# top_tnb_mns_power.net
KiCad netlist of a schematic drawn in Altium Designer
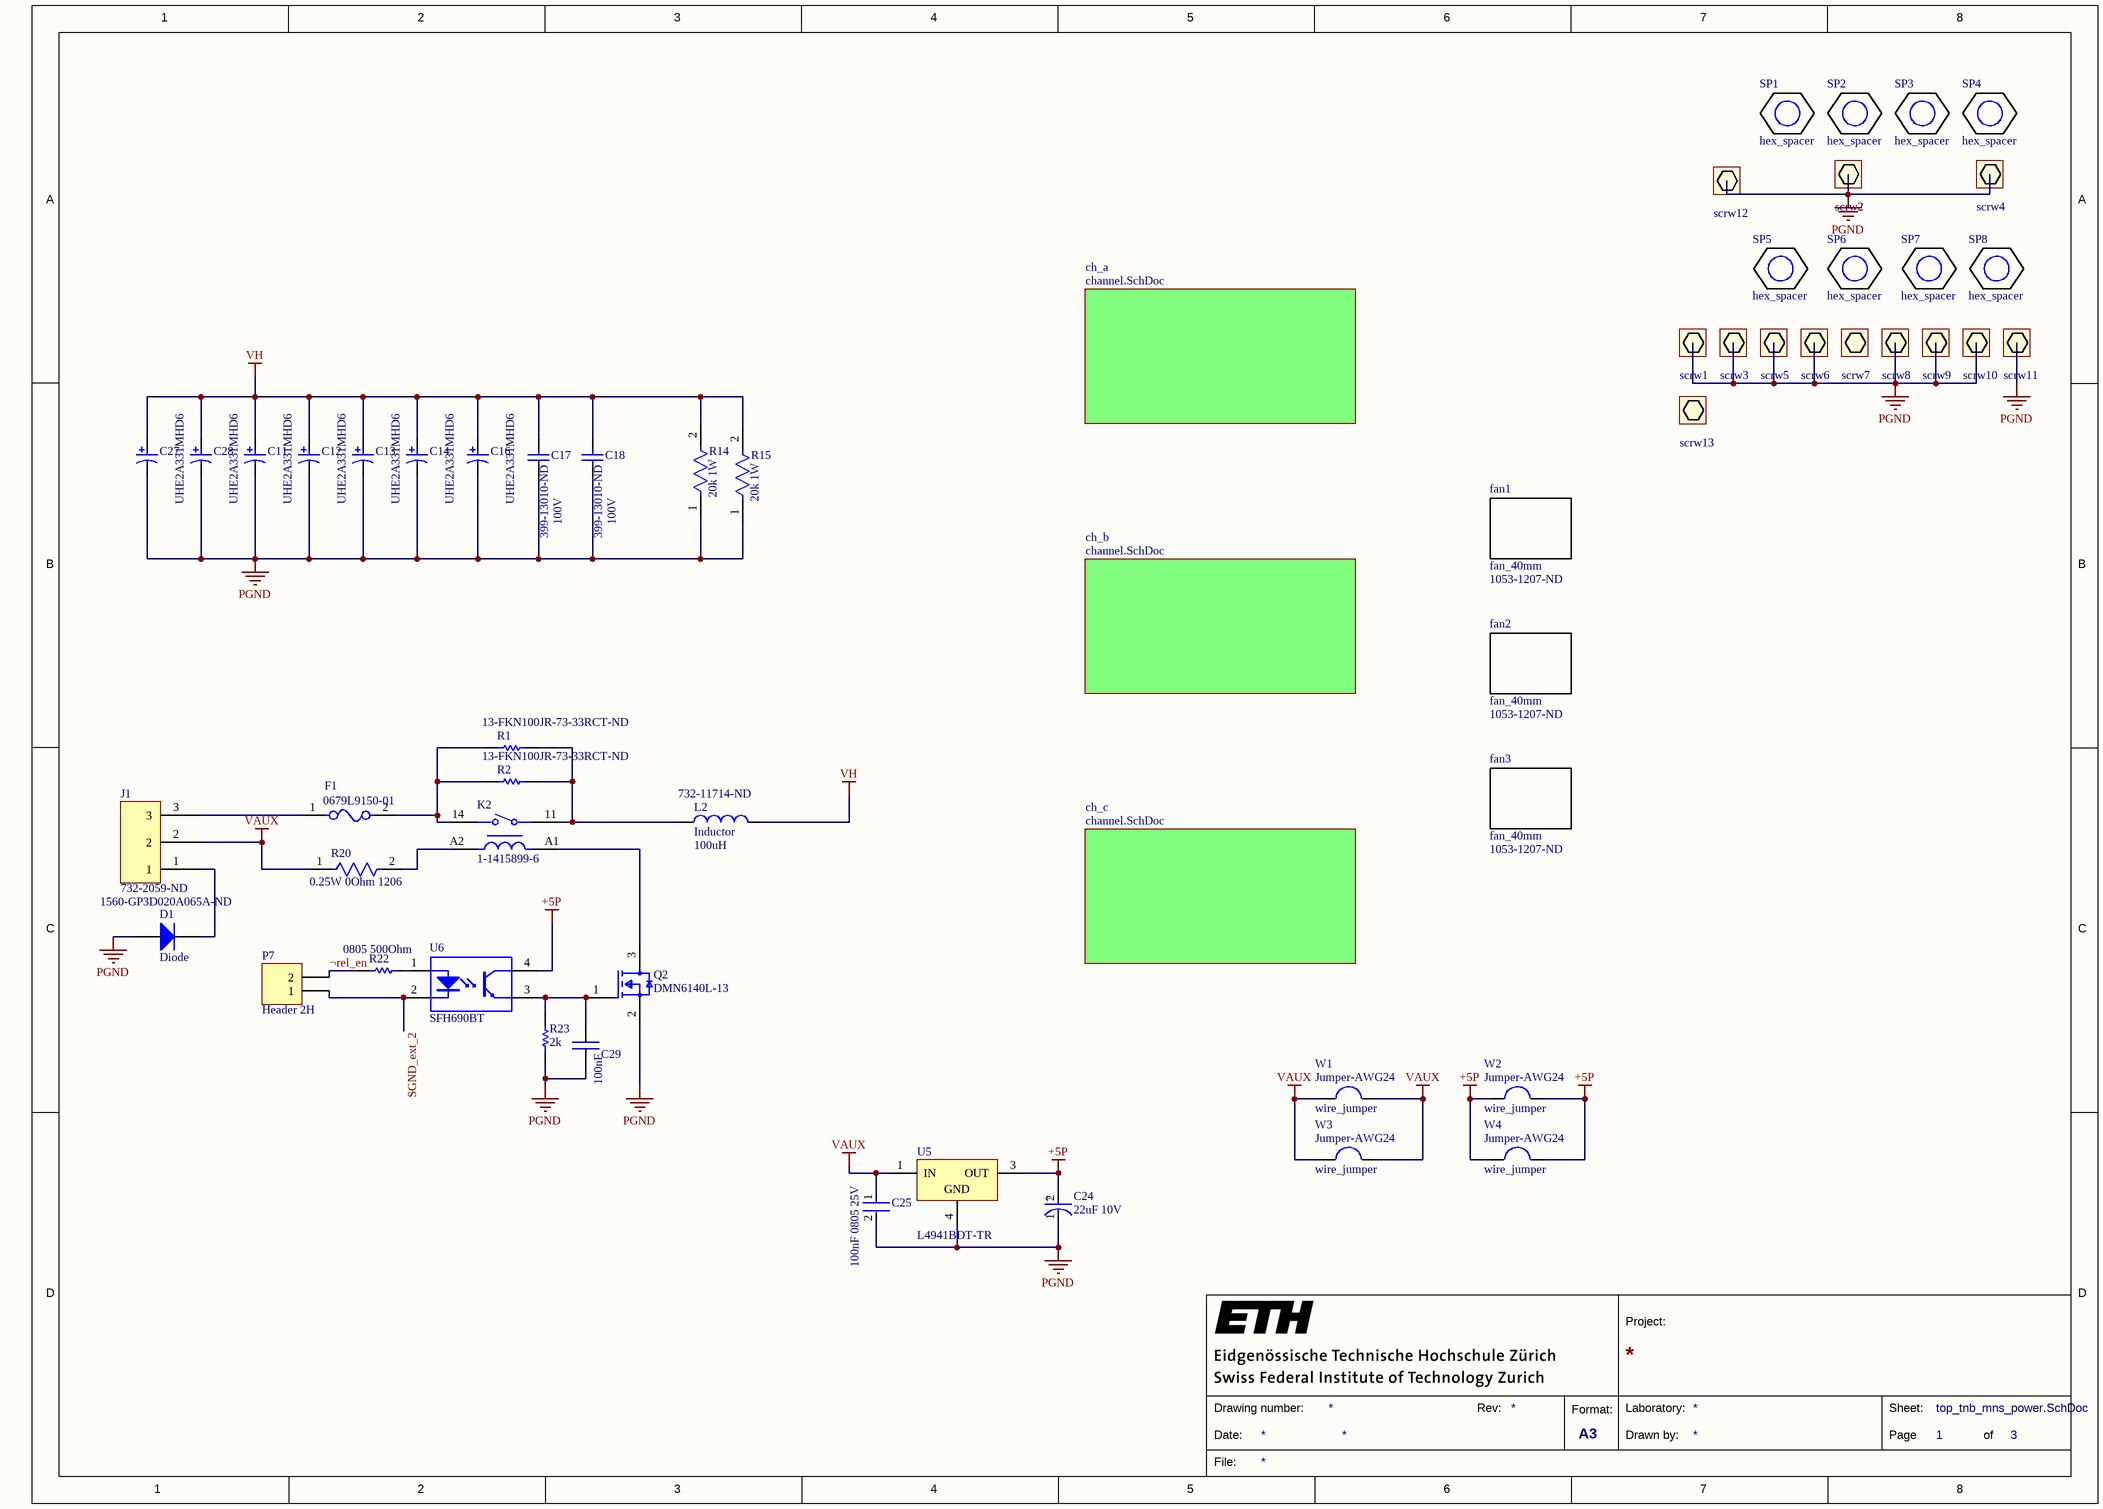
[diagram p0: top_tnb_mns_power.SchDoc]

(export (version "E")
  (design (tool "Eeschema 10.0.6"))
  (components
    (comp (ref "C11")
      (value "UHE2A331MHD6")
      (footprint "CAPPR80-750-2000X1800X2200")
      (description "Aluminum Electrolytic Capacitor, 330 uF, +/- 20%, 100 V, -40 to 105 degC, 2-Pin THD, RoHS, Bulk")
      (fields (field (name "MANUFACTURER") "Nichicon"))
      (libsource (lib "Altium Content Vault") (part "CAP-P-2"))
    )
    (comp (ref "C12")
      (value "UHE2A331MHD6")
      (footprint "CAPPR80-750-2000X1800X2200")
      (description "Aluminum Electrolytic Capacitor, 330 uF, +/- 20%, 100 V, -40 to 105 degC, 2-Pin THD, RoHS, Bulk")
      (fields (field (name "MANUFACTURER") "Nichicon"))
      (libsource (lib "Altium Content Vault") (part "CAP-P-2"))
    )
    (comp (ref "C13")
      (value "UHE2A331MHD6")
      (footprint "CAPPR80-750-2000X1800X2200")
      (description "Aluminum Electrolytic Capacitor, 330 uF, +/- 20%, 100 V, -40 to 105 degC, 2-Pin THD, RoHS, Bulk")
      (fields (field (name "MANUFACTURER") "Nichicon"))
      (libsource (lib "Altium Content Vault") (part "CAP-P-2"))
    )
    (comp (ref "C14")
      (value "UHE2A331MHD6")
      (footprint "CAPPR80-750-2000X1800X2200")
      (description "Aluminum Electrolytic Capacitor, 330 uF, +/- 20%, 100 V, -40 to 105 degC, 2-Pin THD, RoHS, Bulk")
      (fields (field (name "MANUFACTURER") "Nichicon"))
      (libsource (lib "Altium Content Vault") (part "CAP-P-2"))
    )
    (comp (ref "C16")
      (value "UHE2A331MHD6")
      (footprint "CAPPR80-750-2000X1800X2200")
      (description "Aluminum Electrolytic Capacitor, 330 uF, +/- 20%, 100 V, -40 to 105 degC, 2-Pin THD, RoHS, Bulk")
      (fields (field (name "MANUFACTURER") "Nichicon"))
      (libsource (lib "Altium Content Vault") (part "CAP-P-2"))
    )
    (comp (ref "C17")
      (value "100V")
      (footprint "FILM_CAP_100UF_100V_R60EW61005000K")
      (description "Capacitor")
      (fields
        (field (name "SUPPLIER PART NUMBER 1") "399-13010-ND")
        (field (name "PUBLISHER") "Altium Limited")
      )
      (libsource (lib "Miscellaneous Devices") (part "Cap"))
    )
    (comp (ref "C18")
      (value "100V")
      (footprint "FILM_CAP_100UF_100V_R60EW61005000K")
      (description "Capacitor")
      (fields
        (field (name "SUPPLIER PART NUMBER 1") "399-13010-ND")
        (field (name "PUBLISHER") "Altium Limited")
      )
      (libsource (lib "Miscellaneous Devices") (part "Cap"))
    )
    (comp (ref "C24")
      (value "22uF 10V")
      (footprint "FP-T491C226K010AT-MFG")
      (description "CAP TANT 22UF 10% 10V 2312")
      (fields (field (name "TOLERANCE") "20%") (field (name "VOLTAGE") "10V"))
      (libsource (lib "Altium Content Vault") (part "a00bbbee19879c290e62620ae7e47b1"))
    )
    (comp (ref "C25")
      (value "100nF 0805 25V")
      (footprint "FP-CC0805-0_85-MFG")
      (description "CAP CER 0.1UF 25V X7R 0805")
      (fields (field (name "MANUFACTURER PART NUMBER") "CC0805KRX7R8BB104") (field (name "TOLERANCE") "0.1"))
      (libsource (lib "Altium Content Vault") (part "11868f565c42a9108669ba33697ecf6"))
    )
    (comp (ref "C27")
      (value "UHE2A331MHD6")
      (footprint "CAPPR80-750-2000X1800X2200")
      (description "Aluminum Electrolytic Capacitor, 330 uF, +/- 20%, 100 V, -40 to 105 degC, 2-Pin THD, RoHS, Bulk")
      (fields (field (name "MANUFACTURER") "Nichicon"))
      (libsource (lib "Altium Content Vault") (part "CAP-P-2"))
    )
    (comp (ref "C28")
      (value "UHE2A331MHD6")
      (footprint "CAPPR80-750-2000X1800X2200")
      (description "Aluminum Electrolytic Capacitor, 330 uF, +/- 20%, 100 V, -40 to 105 degC, 2-Pin THD, RoHS, Bulk")
      (fields (field (name "MANUFACTURER") "Nichicon"))
      (libsource (lib "Altium Content Vault") (part "CAP-P-2"))
    )
    (comp (ref "C29")
      (value "100nF")
      (footprint "CAP 0603_1608")
      (libsource (lib "coil_driver_lib") (part "cap_smd"))
    )
    (comp (ref "D1")
      (value "Diode")
      (footprint "TO-220-2-bent")
      (description "Default Diode")
      (fields
        (field (name "SUPPLIER PART NUMBER 1") "1560-GP3D020A065A-ND")
        (field (name "PUBLISHER") "Altium Limited")
      )
      (libsource (lib "Miscellaneous Devices") (part "Diode"))
    )
    (comp (ref "F1")
      (value "0679L9150-01")
      (footprint "FP-0679L-MFG")
      (description "FUSE BRD MNT 15A 125VAC/VDC")
      (fields
        (field (name "OCTOPART") "https://octopart.com/0679l9150-01-bel+fuse-70850665")
        (field (name "MANUFACTURER") "Bel Fuse")
      )
      (libsource (lib "Altium Content Vault") (part "5bcf9b9f640e542cf0359d10258e979"))
    )
    (comp (ref "fan1")
      (value "fan_40mm")
      (fields (field (name "SUPPLIER PART NUMBER 1") "1053-1207-ND"))
      (libsource (lib "coil_driver_lib") (part "fan_40mm"))
    )
    (comp (ref "fan2")
      (value "fan_40mm")
      (fields (field (name "SUPPLIER PART NUMBER 1") "1053-1207-ND"))
      (libsource (lib "coil_driver_lib") (part "fan_40mm"))
    )
    (comp (ref "fan3")
      (value "fan_40mm")
      (fields (field (name "SUPPLIER PART NUMBER 1") "1053-1207-ND"))
      (libsource (lib "coil_driver_lib") (part "fan_40mm"))
    )
    (comp (ref "J1")
      (value "20A straight")
      (footprint "691311500103")
      (fields (field (name "SUPPLIER PART NUMBER 1") "732-2059-ND"))
      (libsource (lib "coil_driver_lib") (part "wuerth_connector_straight_30_20A_691311500103"))
    )
    (comp (ref "K2")
      (value "1-1415899-6")
      (footprint "FP-1-1415899-6-MFG")
      (description "RELAY GEN PURPOSE SPST 16A 12V")
      (fields
        (field (name "OCTOPART") "https://octopart.com/1-1415899-6-te+connectivity-46507462")
        (field (name "MANUFACTURER") "TE Connectivity")
      )
      (libsource (lib "Altium Content Vault") (part "36ad11d084bb552319afff42e0065da"))
    )
    (comp (ref "L2")
      (value "Inductor")
      (footprint "wurth_inductor_74437529203101_100uH")
      (fields
        (field (name "ALTIUM_VALUE") "100uH")
        (field (name "SUPPLIER PART NUMBER 1") "732-11714-ND")
        (field (name "PUBLISHER") "Altium Limited")
      )
      (libsource (lib "Miscellaneous Devices") (part "Inductor"))
    )
    (comp (ref "P7")
      (value "Header 2H")
      (footprint "header_2_1_m")
      (description "Header, 2-Pin, Right Angle")
      (fields (field (name "PUBLISHER") "Altium Limited"))
      (libsource (lib "Miscellaneous Connectors") (part "Header 2H"))
    )
    (comp (ref "Q2")
      (value "DMN6140L-13")
      (footprint "FP-SOT23-MFG")
      (description "MOSFET N-CH 60V 1.6A SOT23")
      (fields
        (field (name "OCTOPART") "https://octopart.com/dmn6140l-13-diodes+inc.-38898616")
        (field (name "MANUFACTURER") "Diodes Inc.")
      )
      (libsource (lib "Altium Content Vault") (part "0a9ea7c96deaaede766a5b531c28de0"))
    )
    (comp (ref "R1")
      (value "30Ohm Fusable Resistor")
      (footprint "safety_resistor_30Ohm_1W")
      (description "Resistor")
      (fields
        (field (name "SUPPLIER PART NUMBER 1") "13-FKN100JR-73-33RCT-ND")
        (field (name "PUBLISHER") "Altium Limited")
      )
      (libsource (lib "Miscellaneous Devices") (part "Res1"))
    )
    (comp (ref "R2")
      (value "30Ohm Fusable Resistor")
      (footprint "safety_resistor_30Ohm_1W")
      (description "Resistor")
      (fields
        (field (name "SUPPLIER PART NUMBER 1") "13-FKN100JR-73-33RCT-ND")
        (field (name "PUBLISHER") "Altium Limited")
      )
      (libsource (lib "Miscellaneous Devices") (part "Res1"))
    )
    (comp (ref "R14")
      (value "20k 1W")
      (footprint "FP-CRCW2512-e3-IPC_C")
      (description "RES Thick Film, 20kΩ, 1%, 1W, 100ppm/°C, 2512\r\nCRCW251220K0FKEG")
      (fields (field (name "TOLERANCE") "1%"))
      (libsource (lib "Altium Content Vault") (part "1029c3af85768c4190bb7ad29bc67b5"))
    )
    (comp (ref "R15")
      (value "20k 1W")
      (footprint "FP-CRCW2512-e3-IPC_C")
      (description "RES Thick Film, 20kΩ, 1%, 1W, 100ppm/°C, 2512\r\nCRCW251220K0FKEG")
      (fields (field (name "TOLERANCE") "1%"))
      (libsource (lib "Altium Content Vault") (part "1029c3af85768c4190bb7ad29bc67b5"))
    )
    (comp (ref "R20")
      (value "0.25W 0Ohm 1206")
      (footprint "FP-CRCW1206-e3-MFG")
      (description "RES Thick Film, 100Ω, 1%, 0.25W, 100ppm/°C, 1206\r\nCRCW1206100RFKEA")
      (fields (field (name "TOLERANCE") "1%"))
      (libsource (lib "Altium Content Vault") (part "1029c3af85768c4190bb7ad29bc67b5"))
    )
    (comp (ref "R22")
      (value "0805 500Ohm")
      (footprint "RES 0805_2012")
      (description "Resistor")
      (fields (field (name "PUBLISHER") "Altium Limited"))
      (libsource (lib "Miscellaneous Devices") (part "Res1"))
    )
    (comp (ref "R23")
      (value "2k")
      (footprint "RES 0805_2012")
      (description "Resistor")
      (fields (field (name "PUBLISHER") "Altium Limited"))
      (libsource (lib "Miscellaneous Devices") (part "Res1"))
    )
    (comp (ref "scrw1")
      (value "screw_m2_5")
      (footprint "screw_m2_5")
      (libsource (lib "coil_driver_lib") (part "screw_m2_5"))
    )
    (comp (ref "scrw2")
      (value "screw_m2_5")
      (footprint "screw_m2_5")
      (libsource (lib "coil_driver_lib") (part "screw_m2_5"))
    )
    (comp (ref "scrw3")
      (value "screw_m2_5")
      (footprint "screw_m2_5")
      (libsource (lib "coil_driver_lib") (part "screw_m2_5"))
    )
    (comp (ref "scrw4")
      (value "screw_m2_5")
      (footprint "screw_m2_5")
      (libsource (lib "coil_driver_lib") (part "screw_m2_5"))
    )
    (comp (ref "scrw5")
      (value "screw_m2_5")
      (footprint "screw_m2_5")
      (libsource (lib "coil_driver_lib") (part "screw_m2_5"))
    )
    (comp (ref "scrw6")
      (value "screw_m2_5")
      (footprint "screw_m2_5")
      (libsource (lib "coil_driver_lib") (part "screw_m2_5"))
    )
    (comp (ref "scrw7")
      (value "screw_m2_5")
      (footprint "screw_m2_5")
      (libsource (lib "coil_driver_lib") (part "screw_m2_5"))
    )
    (comp (ref "scrw8")
      (value "screw_m2_5")
      (footprint "screw_m2_5")
      (libsource (lib "coil_driver_lib") (part "screw_m2_5"))
    )
    (comp (ref "scrw9")
      (value "screw_m2_5")
      (footprint "screw_m2_5")
      (libsource (lib "coil_driver_lib") (part "screw_m2_5"))
    )
    (comp (ref "scrw10")
      (value "screw_m2_5")
      (footprint "screw_m2_5")
      (libsource (lib "coil_driver_lib") (part "screw_m2_5"))
    )
    (comp (ref "scrw11")
      (value "screw_m2_5")
      (footprint "screw_m2_5")
      (libsource (lib "coil_driver_lib") (part "screw_m2_5"))
    )
    (comp (ref "scrw12")
      (value "screw_m2_5")
      (footprint "screw_m2_5")
      (libsource (lib "coil_driver_lib") (part "screw_m2_5"))
    )
    (comp (ref "scrw13")
      (value "screw_m2_5")
      (footprint "screw_m2_5")
      (libsource (lib "coil_driver_lib") (part "screw_m2_5"))
    )
    (comp (ref "SP1")
      (value "hex_spacer")
      (footprint "HEX_SPACER _8MM_60MM")
      (libsource (lib "coil_driver_lib") (part "hex_spacer"))
    )
    (comp (ref "SP2")
      (value "hex_spacer")
      (footprint "HEX_SPACER _8MM_60MM")
      (libsource (lib "coil_driver_lib") (part "hex_spacer"))
    )
    (comp (ref "SP3")
      (value "hex_spacer")
      (footprint "HEX_SPACER _8MM_60MM")
      (libsource (lib "coil_driver_lib") (part "hex_spacer"))
    )
    (comp (ref "SP4")
      (value "hex_spacer")
      (footprint "HEX_SPACER _8MM_60MM")
      (libsource (lib "coil_driver_lib") (part "hex_spacer"))
    )
    (comp (ref "SP5")
      (value "hex_spacer")
      (footprint "HEX_SPACER _8MM_60MM")
      (libsource (lib "coil_driver_lib") (part "hex_spacer"))
    )
    (comp (ref "SP6")
      (value "hex_spacer")
      (footprint "HEX_SPACER _8MM_60MM")
      (libsource (lib "coil_driver_lib") (part "hex_spacer"))
    )
    (comp (ref "SP7")
      (value "hex_spacer")
      (footprint "HEX_SPACER _8MM_60MM")
      (libsource (lib "coil_driver_lib") (part "hex_spacer"))
    )
    (comp (ref "SP8")
      (value "hex_spacer")
      (footprint "HEX_SPACER _8MM_60MM")
      (libsource (lib "coil_driver_lib") (part "hex_spacer"))
    )
    (comp (ref "U5")
      (value "L4941BDT-TR")
      (footprint "TO-252_L")
      (description "1A Very Low Drop Regulator, 3-Pin DPAK, Tape and Reel")
      (libsource (lib "Altium Content Vault") (part "PM-REG-L4940-SOT3"))
    )
    (comp (ref "U6")
      (value "SFH690BT")
      (footprint "VISH-SOP-4_A_V")
      (description "Optocoupler Phototransistor Output, 6 V, 50 mA, -55 to 100 degC, 4-Pin SOIC, RoHS, Tape and Reel")
      (fields (field (name "MANUFACTURER") "Vishay"))
      (libsource (lib "Altium Content Vault") (part "OPTO-AKEC-4"))
    )
    (comp (ref "W1")
      (value "wire_jumper")
      (footprint "wire_jumper")
      (libsource (lib "coil_driver_lib") (part "wire_jumper"))
    )
    (comp (ref "W2")
      (value "wire_jumper")
      (footprint "wire_jumper")
      (libsource (lib "coil_driver_lib") (part "wire_jumper"))
    )
    (comp (ref "W3")
      (value "wire_jumper")
      (footprint "wire_jumper")
      (libsource (lib "coil_driver_lib") (part "wire_jumper"))
    )
    (comp (ref "W4")
      (value "wire_jumper")
      (footprint "wire_jumper")
      (libsource (lib "coil_driver_lib") (part "wire_jumper"))
    )
  )
  (nets
    (net (code "1") (name "+5P") (class "Default")
      (node (ref "C24") (pin "2") (pinfunction "A_2") (pintype "passive"))
      (node (ref "U5") (pin "3") (pinfunction "OUT_3") (pintype "power_in"))
      (node (ref "U6") (pin "4") (pinfunction "COLLECTOR_4") (pintype "passive"))
      (node (ref "W2") (pin "1") (pinfunction "1_1") (pintype "passive"))
      (node (ref "W2") (pin "2") (pinfunction "2_2") (pintype "passive"))
      (node (ref "W4") (pin "1") (pinfunction "1_1") (pintype "passive"))
      (node (ref "W4") (pin "2") (pinfunction "2_2") (pintype "passive"))
    )
    (net (code "2") (name "/SGND_ext_2") (class "Default")
      (node (ref "P7") (pin "1") (pinfunction "1_1") (pintype "passive"))
      (node (ref "U6") (pin "2") (pinfunction "CATHODE_2") (pintype "passive"))
    )
    (net (code "3") (name "/¬rel_en") (class "Default")
      (node (ref "P7") (pin "2") (pinfunction "2_2") (pintype "passive"))
      (node (ref "R22") (pin "1") (pinfunction "1_1") (pintype "passive"))
    )
    (net (code "4") (name "Net-(D1-K)") (class "Default")
      (node (ref "D1") (pin "2") (pinfunction "K_2") (pintype "passive"))
      (node (ref "J1") (pin "1") (pinfunction "1_1") (pintype "passive"))
    )
    (net (code "5") (name "Net-(F1-Pad1)") (class "Default")
      (node (ref "F1") (pin "1") (pinfunction "1_1") (pintype "passive"))
      (node (ref "J1") (pin "3") (pinfunction "3_3") (pintype "passive"))
    )
    (net (code "6") (name "Net-(F1-Pad2)") (class "Default")
      (node (ref "F1") (pin "2") (pinfunction "2_2") (pintype "passive"))
      (node (ref "K2") (pin "14") (pinfunction "14_14") (pintype "passive"))
      (node (ref "R1") (pin "1") (pinfunction "1_1") (pintype "passive"))
      (node (ref "R2") (pin "1") (pinfunction "1_1") (pintype "passive"))
    )
    (net (code "7") (name "Net-(K2-Pad11)") (class "Default")
      (node (ref "K2") (pin "11") (pinfunction "11_11") (pintype "passive"))
      (node (ref "L2") (pin "1") (pinfunction "1_1") (pintype "passive"))
      (node (ref "R1") (pin "2") (pinfunction "2_2") (pintype "passive"))
      (node (ref "R2") (pin "2") (pinfunction "2_2") (pintype "passive"))
    )
    (net (code "8") (name "Net-(K2-PadA2)") (class "Default")
      (node (ref "K2") (pin "A2") (pinfunction "A2_A2") (pintype "passive"))
      (node (ref "R20") (pin "2") (pinfunction "2_2") (pintype "passive"))
    )
    (net (code "9") (name "Net-(Q2-D)") (class "Default")
      (node (ref "K2") (pin "A1") (pinfunction "A1_A1") (pintype "passive"))
      (node (ref "Q2") (pin "3") (pinfunction "D_3") (pintype "passive"))
    )
    (net (code "10") (name "Net-(Q2-G)") (class "Default")
      (node (ref "C29") (pin "1") (pinfunction "1_1") (pintype "passive"))
      (node (ref "Q2") (pin "1") (pinfunction "G_1") (pintype "passive"))
      (node (ref "R23") (pin "2") (pinfunction "2_2") (pintype "passive"))
      (node (ref "U6") (pin "3") (pinfunction "EMITTER_3") (pintype "passive"))
    )
    (net (code "11") (name "Net-(U6-ANODE)") (class "Default")
      (node (ref "R22") (pin "2") (pinfunction "2_2") (pintype "passive"))
      (node (ref "U6") (pin "1") (pinfunction "ANODE_1") (pintype "passive"))
    )
    (net (code "12") (name "PGND") (class "Default")
      (node (ref "C11") (pin "2") (pinfunction "2_2") (pintype "passive"))
      (node (ref "C12") (pin "2") (pinfunction "2_2") (pintype "passive"))
      (node (ref "C13") (pin "2") (pinfunction "2_2") (pintype "passive"))
      (node (ref "C14") (pin "2") (pinfunction "2_2") (pintype "passive"))
      (node (ref "C16") (pin "2") (pinfunction "2_2") (pintype "passive"))
      (node (ref "C17") (pin "1") (pinfunction "1_1") (pintype "passive"))
      (node (ref "C18") (pin "1") (pinfunction "1_1") (pintype "passive"))
      (node (ref "C24") (pin "1") (pinfunction "C_1") (pintype "passive"))
      (node (ref "C25") (pin "2") (pinfunction "2_2") (pintype "passive"))
      (node (ref "C27") (pin "2") (pinfunction "2_2") (pintype "passive"))
      (node (ref "C28") (pin "2") (pinfunction "2_2") (pintype "passive"))
      (node (ref "C29") (pin "2") (pinfunction "2_2") (pintype "passive"))
      (node (ref "D1") (pin "1") (pinfunction "A_1") (pintype "passive"))
      (node (ref "Q2") (pin "2") (pinfunction "S_2") (pintype "passive"))
      (node (ref "R14") (pin "1") (pinfunction "1_1") (pintype "passive"))
      (node (ref "R15") (pin "1") (pinfunction "1_1") (pintype "passive"))
      (node (ref "R23") (pin "1") (pinfunction "1_1") (pintype "passive"))
      (node (ref "U5") (pin "4") (pinfunction "GND_4") (pintype "power_in"))
      (node (ref "scrw1") (pin "1") (pinfunction "1_1") (pintype "passive"))
      (node (ref "scrw10") (pin "1") (pinfunction "1_1") (pintype "passive"))
      (node (ref "scrw11") (pin "1") (pinfunction "1_1") (pintype "passive"))
      (node (ref "scrw12") (pin "1") (pinfunction "1_1") (pintype "passive"))
      (node (ref "scrw2") (pin "1") (pinfunction "1_1") (pintype "passive"))
      (node (ref "scrw3") (pin "1") (pinfunction "1_1") (pintype "passive"))
      (node (ref "scrw4") (pin "1") (pinfunction "1_1") (pintype "passive"))
      (node (ref "scrw5") (pin "1") (pinfunction "1_1") (pintype "passive"))
      (node (ref "scrw6") (pin "1") (pinfunction "1_1") (pintype "passive"))
      (node (ref "scrw8") (pin "1") (pinfunction "1_1") (pintype "passive"))
      (node (ref "scrw9") (pin "1") (pinfunction "1_1") (pintype "passive"))
    )
    (net (code "13") (name "VAUX") (class "Default")
      (node (ref "C25") (pin "1") (pinfunction "1_1") (pintype "passive"))
      (node (ref "J1") (pin "2") (pinfunction "2_2") (pintype "passive"))
      (node (ref "R20") (pin "1") (pinfunction "1_1") (pintype "passive"))
      (node (ref "U5") (pin "1") (pinfunction "IN_1") (pintype "power_in"))
      (node (ref "W1") (pin "1") (pinfunction "1_1") (pintype "passive"))
      (node (ref "W1") (pin "2") (pinfunction "2_2") (pintype "passive"))
      (node (ref "W3") (pin "1") (pinfunction "1_1") (pintype "passive"))
      (node (ref "W3") (pin "2") (pinfunction "2_2") (pintype "passive"))
    )
    (net (code "14") (name "VH") (class "Default")
      (node (ref "C11") (pin "1") (pinfunction "1_1") (pintype "passive"))
      (node (ref "C12") (pin "1") (pinfunction "1_1") (pintype "passive"))
      (node (ref "C13") (pin "1") (pinfunction "1_1") (pintype "passive"))
      (node (ref "C14") (pin "1") (pinfunction "1_1") (pintype "passive"))
      (node (ref "C16") (pin "1") (pinfunction "1_1") (pintype "passive"))
      (node (ref "C17") (pin "2") (pinfunction "2_2") (pintype "passive"))
      (node (ref "C18") (pin "2") (pinfunction "2_2") (pintype "passive"))
      (node (ref "C27") (pin "1") (pinfunction "1_1") (pintype "passive"))
      (node (ref "C28") (pin "1") (pinfunction "1_1") (pintype "passive"))
      (node (ref "L2") (pin "2") (pinfunction "2_2") (pintype "passive"))
      (node (ref "R14") (pin "2") (pinfunction "2_2") (pintype "passive"))
      (node (ref "R15") (pin "2") (pinfunction "2_2") (pintype "passive"))
    )
    (net (code "15") (name "unconnected-(scrw7-Pad1)") (class "Default")
      (node (ref "scrw7") (pin "1") (pinfunction "1_1") (pintype "passive"))
    )
    (net (code "16") (name "unconnected-(scrw13-Pad1)") (class "Default")
      (node (ref "scrw13") (pin "1") (pinfunction "1_1") (pintype "passive"))
    )
  )
)
